# Stepper_Motor3.net
KiCad netlist of a schematic drawn in Altium Designer
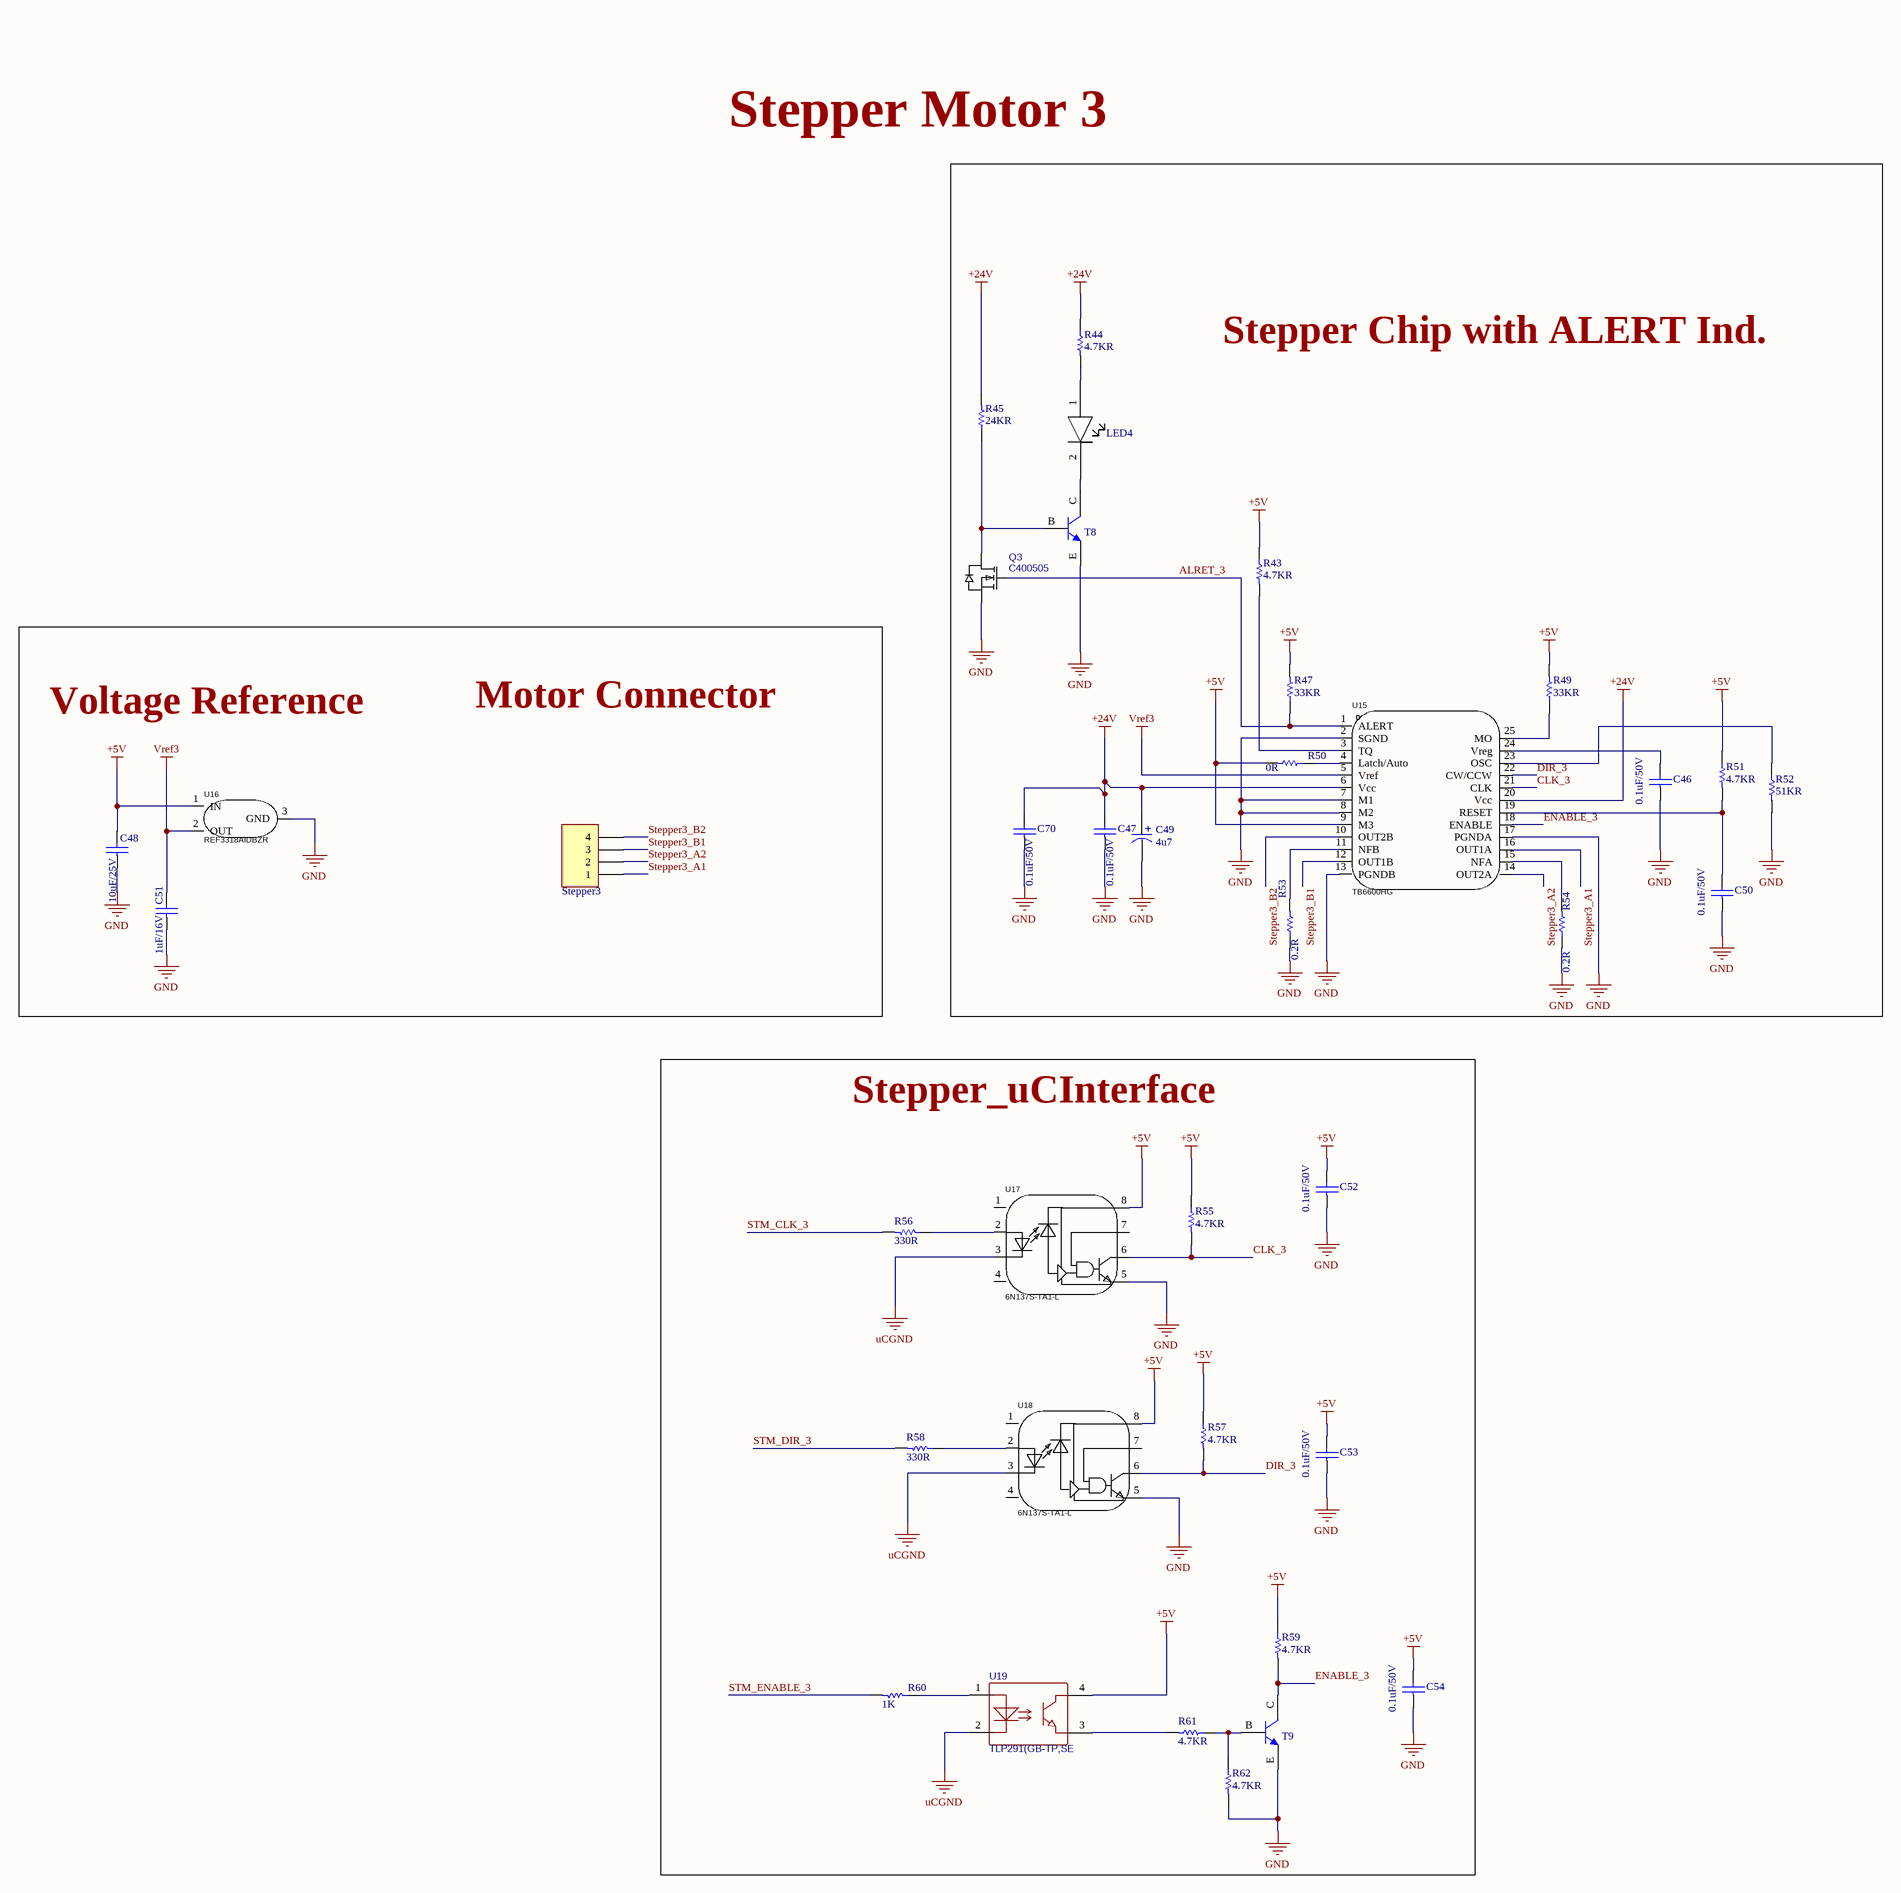
[diagram p0: Stepper Motor3.SchDoc]

(export (version "E")
  (design (tool "Eeschema 10.0.6"))
  (components
    (comp (ref "C46")
      (value "0.1uF/50V")
      (footprint "PCBComponent_1")
      (description "C1591")
      (fields (field (name "CREATED BY") "NourAldin"))
      (libsource (lib "0603 Capacitor") (part "0603 Capacitor"))
    )
    (comp (ref "C47")
      (value "0.1uF/50V")
      (footprint "PCBComponent_1")
      (description "C1591")
      (fields (field (name "CREATED BY") "NourAldin"))
      (libsource (lib "0603 Capacitor") (part "0603 Capacitor"))
    )
    (comp (ref "C48")
      (value "10uF/25V")
      (footprint "PCBComponent_1")
      (description "C96446")
      (fields (field (name "CREATED BY") "NourAldin"))
      (libsource (lib "0603 Capacitor") (part "0603 Capacitor"))
    )
    (comp (ref "C49")
      (value "4u7")
      (footprint "CAPLEAD_D6.3mm")
      (description "C2691843")
      (fields
        (field (name "MANUFACTURER") "KEMET")
        (field (name "MANUFACTURER PART NUMBER") "A759EQ475M2AAAE160")
      )
      (libsource (lib "GlobalLib") (part "A759EQ475M2AAAE160"))
    )
    (comp (ref "C50")
      (value "0.1uF/50V")
      (footprint "PCBComponent_1")
      (description "C1591")
      (fields (field (name "CREATED BY") "NourAldin"))
      (libsource (lib "0603 Capacitor") (part "0603 Capacitor"))
    )
    (comp (ref "C51")
      (value "1uF/16V")
      (footprint "PCBComponent_1")
      (description "C1592")
      (fields (field (name "CREATED BY") "NourAldin"))
      (libsource (lib "0603 Capacitor") (part "0603 Capacitor"))
    )
    (comp (ref "C52")
      (value "0.1uF/50V")
      (footprint "PCBComponent_1")
      (description "C1591")
      (fields (field (name "CREATED BY") "NourAldin"))
      (libsource (lib "0603 Capacitor") (part "0603 Capacitor"))
    )
    (comp (ref "C53")
      (value "0.1uF/50V")
      (footprint "PCBComponent_1")
      (description "C1591")
      (fields (field (name "CREATED BY") "NourAldin"))
      (libsource (lib "0603 Capacitor") (part "0603 Capacitor"))
    )
    (comp (ref "C54")
      (value "0.1uF/50V")
      (footprint "PCBComponent_1")
      (description "C1591")
      (fields (field (name "CREATED BY") "NourAldin"))
      (libsource (lib "0603 Capacitor") (part "0603 Capacitor"))
    )
    (comp (ref "C70")
      (value "0.1uF/50V")
      (footprint "PCBComponent_1")
      (description "C1591")
      (fields (field (name "CREATED BY") "NourAldin"))
      (libsource (lib "0603 Capacitor") (part "0603 Capacitor"))
    )
    (comp (ref "LED4")
      (value "1206 LED")
      (footprint "1206 LED")
      (description "C434438")
      (fields (field (name "CREATED BY") "NourAldin"))
      (libsource (lib "1206 LED") (part "1206 LED"))
    )
    (comp (ref "Q3")
      (value "C400505")
      (footprint "SOT-23-3_L2.9-W1.3-P1.90-LS2.4-BR")
      (fields
        (field (name "MANUFACTURER") "YANGJIE(扬杰)")
        (field (name "MANUFACTURER PART") "BSS138")
        (field (name "CONTRIBUTOR") "LCSC")
      )
      (libsource (lib "DIVERSE") (part "BSS138_MOSFET"))
    )
    (comp (ref "R43")
      (value "4.7KR")
      (footprint "R0402")
      (description "C105871")
      (libsource (lib "DIVERSE") (part "0402 Resistor"))
    )
    (comp (ref "R44")
      (value "4.7KR")
      (footprint "R0402")
      (description "C105871")
      (libsource (lib "DIVERSE") (part "0402 Resistor"))
    )
    (comp (ref "R45")
      (value "24KR")
      (footprint "RESC1608X06N")
      (description "C2930081")
      (fields (field (name "CREATED BY") "NourAldin"))
      (libsource (lib "0603 Resistor") (part "0603 Resistor"))
    )
    (comp (ref "R47")
      (value "33KR")
      (footprint "RESC1608X06N")
      (description "C126359")
      (fields (field (name "CREATED BY") "NourAldin"))
      (libsource (lib "0603 Resistor") (part "0603 Resistor"))
    )
    (comp (ref "R49")
      (value "33KR")
      (footprint "RESC1608X06N")
      (description "C126359")
      (fields (field (name "CREATED BY") "NourAldin"))
      (libsource (lib "0603 Resistor") (part "0603 Resistor"))
    )
    (comp (ref "R50")
      (value "0R")
      (footprint "RESC1608X06N")
      (description "C100044")
      (fields (field (name "CREATED BY") "NourAldin"))
      (libsource (lib "0603 Resistor") (part "0603 Resistor"))
    )
    (comp (ref "R51")
      (value "4.7KR")
      (footprint "R0402")
      (description "C105871")
      (libsource (lib "DIVERSE") (part "0402 Resistor"))
    )
    (comp (ref "R52")
      (value "51KR")
      (footprint "R0402")
      (description "C107230")
      (libsource (lib "DIVERSE") (part "0402 Resistor"))
    )
    (comp (ref "R53")
      (value "0.2R")
      (footprint "RESC6431X12N")
      (description "C2903473")
      (fields (field (name "CREATED BY") "NourAldin"))
      (libsource (lib "2512 Resistor") (part "2512 Resistor"))
    )
    (comp (ref "R54")
      (value "0.2R")
      (footprint "RESC6431X12N")
      (description "C2903473")
      (fields (field (name "CREATED BY") "NourAldin"))
      (libsource (lib "2512 Resistor") (part "2512 Resistor"))
    )
    (comp (ref "R55")
      (value "4.7KR")
      (footprint "R0402")
      (description "C105871")
      (libsource (lib "DIVERSE") (part "0402 Resistor"))
    )
    (comp (ref "R56")
      (value "330R")
      (footprint "R0402")
      (description "C105875")
      (libsource (lib "DIVERSE") (part "0402 Resistor"))
    )
    (comp (ref "R57")
      (value "4.7KR")
      (footprint "R0402")
      (description "C105871")
      (libsource (lib "DIVERSE") (part "0402 Resistor"))
    )
    (comp (ref "R58")
      (value "330R")
      (footprint "R0402")
      (description "C105875")
      (libsource (lib "DIVERSE") (part "0402 Resistor"))
    )
    (comp (ref "R59")
      (value "4.7KR")
      (footprint "R0402")
      (description "C105871")
      (libsource (lib "DIVERSE") (part "0402 Resistor"))
    )
    (comp (ref "R60")
      (value "1K")
      (footprint "R0402")
      (description "C106235")
      (libsource (lib "DIVERSE") (part "0402 Resistor"))
    )
    (comp (ref "R61")
      (value "4.7KR")
      (footprint "R0402")
      (description "C105871")
      (libsource (lib "DIVERSE") (part "0402 Resistor"))
    )
    (comp (ref "R62")
      (value "4.7KR")
      (footprint "R0402")
      (description "C105871")
      (libsource (lib "DIVERSE") (part "0402 Resistor"))
    )
    (comp (ref "Stepper3")
      (value "Header 4 Pin Polar")
      (footprint "PCBComponent_1")
      (description "C144395")
      (libsource (lib "Header 4 Pin Polar") (part "Header 4 Pin Polar"))
    )
    (comp (ref "T8")
      (value "MMBT3904 Transistor")
      (footprint "MMBT3904")
      (description "C108429")
      (fields (field (name "CREATED BY") "NourAldin"))
      (libsource (lib "MMBT3904 Transistor") (part "MMBT3904 Transistor"))
    )
    (comp (ref "T9")
      (value "MMBT3904 Transistor")
      (footprint "MMBT3904")
      (description "C108429")
      (fields (field (name "CREATED BY") "NourAldin"))
      (libsource (lib "MMBT3904 Transistor") (part "MMBT3904 Transistor"))
    )
    (comp (ref "U15")
      (value "TB6600HG")
      (footprint "HZIP25-P-1.0_TB6600HG - HEATSINK")
      (description "C66042")
      (fields (field (name "MANUFACTURER") "TOSHIBA(东芝)"))
      (libsource (lib "LIB") (part "TB6600HG"))
    )
    (comp (ref "U16")
      (value "REF3318AIDBZR")
      (footprint "SOT-23-3_L2.9-W1.3-P1.90-LS2.4-BR")
      (description "C115877")
      (fields (field (name "MANUFACTURER") "TI(德州仪器)") (field (name "TOLERANCE") "±0.15%"))
      (libsource (lib "LIB") (part "REF3318AIDBZR"))
    )
    (comp (ref "U17")
      (value "6N137S-TA1-L")
      (footprint "SOP-8_L9.8-W6.6-P2.54-LS10.3-BL")
      (description "C92651")
      (fields (field (name "MANUFACTURER") "LITEON(光宝)"))
      (libsource (lib "LIB") (part "6N137S-TA1-L"))
    )
    (comp (ref "U18")
      (value "6N137S-TA1-L")
      (footprint "SOP-8_L9.8-W6.6-P2.54-LS10.3-BL")
      (description "C92651")
      (fields (field (name "MANUFACTURER") "LITEON(光宝)"))
      (libsource (lib "LIB") (part "6N137S-TA1-L"))
    )
    (comp (ref "U19")
      (value "TLP291(GB-TP,SE")
      (footprint "SOP-4-1.27mm")
      (description "C55144")
      (libsource (lib "CO2_Lib") (part "TLP291(GB-TP,SE(T"))
    )
  )
  (nets
    (net (code "1") (name "+5V") (class "Default")
      (node (ref "C48") (pin "2") (pinfunction "2_2") (pintype "passive"))
      (node (ref "C52") (pin "2") (pinfunction "2_2") (pintype "passive"))
      (node (ref "C53") (pin "2") (pinfunction "2_2") (pintype "passive"))
      (node (ref "C54") (pin "2") (pinfunction "2_2") (pintype "passive"))
      (node (ref "R43") (pin "1") (pinfunction "1_1") (pintype "passive"))
      (node (ref "R47") (pin "2") (pinfunction "2_2") (pintype "passive"))
      (node (ref "R49") (pin "2") (pinfunction "2_2") (pintype "passive"))
      (node (ref "R50") (pin "2") (pinfunction "2_2") (pintype "passive"))
      (node (ref "R51") (pin "1") (pinfunction "1_1") (pintype "passive"))
      (node (ref "R55") (pin "1") (pinfunction "1_1") (pintype "passive"))
      (node (ref "R57") (pin "1") (pinfunction "1_1") (pintype "passive"))
      (node (ref "R59") (pin "1") (pinfunction "1_1") (pintype "passive"))
      (node (ref "U15") (pin "9") (pinfunction "M3_9") (pintype "passive"))
      (node (ref "U16") (pin "1") (pinfunction "IN_1") (pintype "passive"))
      (node (ref "U17") (pin "8") (pinfunction "8_8") (pintype "passive"))
      (node (ref "U18") (pin "8") (pinfunction "8_8") (pintype "passive"))
      (node (ref "U19") (pin "4") (pinfunction "4_4") (pintype "passive"))
    )
    (net (code "2") (name "+24V") (class "Default")
      (node (ref "C47") (pin "2") (pinfunction "2_2") (pintype "passive"))
      (node (ref "C49") (pin "1") (pinfunction "1_1") (pintype "passive"))
      (node (ref "C70") (pin "2") (pinfunction "2_2") (pintype "passive"))
      (node (ref "R44") (pin "1") (pinfunction "1_1") (pintype "passive"))
      (node (ref "R45") (pin "2") (pinfunction "2_2") (pintype "passive"))
      (node (ref "U15") (pin "20") (pinfunction "Vcc_20") (pintype "passive"))
      (node (ref "U15") (pin "6") (pinfunction "Vcc_6") (pintype "passive"))
    )
    (net (code "3") (name "/ALRET_3") (class "Default")
      (node (ref "Q3") (pin "1") (pinfunction "G_1") (pintype "passive"))
      (node (ref "R47") (pin "1") (pinfunction "1_1") (pintype "passive"))
      (node (ref "U15") (pin "1") (pinfunction "ALERT_1") (pintype "passive"))
    )
    (net (code "4") (name "/CLK_3") (class "Default")
      (node (ref "R55") (pin "2") (pinfunction "2_2") (pintype "passive"))
      (node (ref "U15") (pin "21") (pinfunction "CLK_21") (pintype "passive"))
      (node (ref "U17") (pin "6") (pinfunction "6_6") (pintype "passive"))
    )
    (net (code "5") (name "/DIR_3") (class "Default")
      (node (ref "R57") (pin "2") (pinfunction "2_2") (pintype "passive"))
      (node (ref "U15") (pin "22") (pinfunction "CW/CCW_22") (pintype "passive"))
      (node (ref "U18") (pin "6") (pinfunction "6_6") (pintype "passive"))
    )
    (net (code "6") (name "/ENABLE_3") (class "Default")
      (node (ref "R59") (pin "2") (pinfunction "2_2") (pintype "passive"))
      (node (ref "T9") (pin "C") (pinfunction "C_C") (pintype "passive"))
      (node (ref "U15") (pin "18") (pinfunction "ENABLE_18") (pintype "passive"))
    )
    (net (code "7") (name "/STM_CLK_3") (class "Default")
      (node (ref "R56") (pin "2") (pinfunction "2_2") (pintype "passive"))
    )
    (net (code "8") (name "/STM_DIR_3") (class "Default")
      (node (ref "R58") (pin "2") (pinfunction "2_2") (pintype "passive"))
    )
    (net (code "9") (name "/STM_ENABLE_3") (class "Default")
      (node (ref "R60") (pin "2") (pinfunction "2_2") (pintype "passive"))
    )
    (net (code "10") (name "/Stepper3_A1") (class "Default")
      (node (ref "Stepper3") (pin "1") (pinfunction "1_1") (pintype "passive"))
      (node (ref "U15") (pin "16") (pinfunction "OUT1A_16") (pintype "passive"))
    )
    (net (code "11") (name "/Stepper3_A2") (class "Default")
      (node (ref "Stepper3") (pin "2") (pinfunction "2_2") (pintype "passive"))
      (node (ref "U15") (pin "14") (pinfunction "OUT2A_14") (pintype "passive"))
    )
    (net (code "12") (name "/Stepper3_B1") (class "Default")
      (node (ref "Stepper3") (pin "3") (pinfunction "3_3") (pintype "passive"))
      (node (ref "U15") (pin "12") (pinfunction "OUT1B_12") (pintype "passive"))
    )
    (net (code "13") (name "/Stepper3_B2") (class "Default")
      (node (ref "Stepper3") (pin "4") (pinfunction "4_4") (pintype "passive"))
      (node (ref "U15") (pin "10") (pinfunction "OUT2B_10") (pintype "passive"))
    )
    (net (code "14") (name "GND") (class "Default")
      (node (ref "C46") (pin "1") (pinfunction "1_1") (pintype "passive"))
      (node (ref "C47") (pin "1") (pinfunction "1_1") (pintype "passive"))
      (node (ref "C48") (pin "1") (pinfunction "1_1") (pintype "passive"))
      (node (ref "C49") (pin "2") (pinfunction "2_2") (pintype "passive"))
      (node (ref "C50") (pin "1") (pinfunction "1_1") (pintype "passive"))
      (node (ref "C51") (pin "1") (pinfunction "1_1") (pintype "passive"))
      (node (ref "C52") (pin "1") (pinfunction "1_1") (pintype "passive"))
      (node (ref "C53") (pin "1") (pinfunction "1_1") (pintype "passive"))
      (node (ref "C54") (pin "1") (pinfunction "1_1") (pintype "passive"))
      (node (ref "C70") (pin "1") (pinfunction "1_1") (pintype "passive"))
      (node (ref "Q3") (pin "2") (pinfunction "S_2") (pintype "passive"))
      (node (ref "R52") (pin "2") (pinfunction "2_2") (pintype "passive"))
      (node (ref "R53") (pin "1") (pinfunction "1_1") (pintype "passive"))
      (node (ref "R54") (pin "1") (pinfunction "1_1") (pintype "passive"))
      (node (ref "R62") (pin "2") (pinfunction "2_2") (pintype "passive"))
      (node (ref "T8") (pin "E") (pinfunction "E_E") (pintype "passive"))
      (node (ref "T9") (pin "E") (pinfunction "E_E") (pintype "passive"))
      (node (ref "U15") (pin "13") (pinfunction "PGNDB_13") (pintype "passive"))
      (node (ref "U15") (pin "17") (pinfunction "PGNDA_17") (pintype "passive"))
      (node (ref "U15") (pin "2") (pinfunction "SGND_2") (pintype "passive"))
      (node (ref "U15") (pin "7") (pinfunction "M1_7") (pintype "passive"))
      (node (ref "U15") (pin "8") (pinfunction "M2_8") (pintype "passive"))
      (node (ref "U16") (pin "3") (pinfunction "GND_3") (pintype "passive"))
      (node (ref "U17") (pin "5") (pinfunction "5_5") (pintype "passive"))
      (node (ref "U18") (pin "5") (pinfunction "5_5") (pintype "passive"))
    )
    (net (code "15") (name "Net-(LED4-Pad1)") (class "Default")
      (node (ref "LED4") (pin "1") (pinfunction "1_1") (pintype "passive"))
      (node (ref "R44") (pin "2") (pinfunction "2_2") (pintype "passive"))
    )
    (net (code "16") (name "Net-(LED4-Pad2)") (class "Default")
      (node (ref "LED4") (pin "2") (pinfunction "2_2") (pintype "passive"))
      (node (ref "T8") (pin "C") (pinfunction "C_C") (pintype "passive"))
    )
    (net (code "17") (name "Net-(Q3-D)") (class "Default")
      (node (ref "Q3") (pin "3") (pinfunction "D_3") (pintype "passive"))
      (node (ref "R45") (pin "1") (pinfunction "1_1") (pintype "passive"))
      (node (ref "T8") (pin "B") (pinfunction "B_B") (pintype "passive"))
    )
    (net (code "18") (name "Net-(R56-Pad1)") (class "Default")
      (node (ref "R56") (pin "1") (pinfunction "1_1") (pintype "passive"))
      (node (ref "U17") (pin "2") (pinfunction "2_2") (pintype "passive"))
    )
    (net (code "19") (name "Net-(R58-Pad1)") (class "Default")
      (node (ref "R58") (pin "1") (pinfunction "1_1") (pintype "passive"))
      (node (ref "U18") (pin "2") (pinfunction "2_2") (pintype "passive"))
    )
    (net (code "20") (name "Net-(R60-Pad1)") (class "Default")
      (node (ref "R60") (pin "1") (pinfunction "1_1") (pintype "passive"))
      (node (ref "U19") (pin "1") (pinfunction "1_1") (pintype "passive"))
    )
    (net (code "21") (name "Net-(R61-Pad1)") (class "Default")
      (node (ref "R61") (pin "1") (pinfunction "1_1") (pintype "passive"))
      (node (ref "R62") (pin "1") (pinfunction "1_1") (pintype "passive"))
      (node (ref "T9") (pin "B") (pinfunction "B_B") (pintype "passive"))
    )
    (net (code "22") (name "Net-(R61-Pad2)") (class "Default")
      (node (ref "R61") (pin "2") (pinfunction "2_2") (pintype "passive"))
      (node (ref "U19") (pin "3") (pinfunction "3_3") (pintype "passive"))
    )
    (net (code "23") (name "Net-(U15-Latch{slash}Auto)") (class "Default")
      (node (ref "R50") (pin "1") (pinfunction "1_1") (pintype "passive"))
      (node (ref "U15") (pin "4") (pinfunction "Latch/Auto_4") (pintype "passive"))
    )
    (net (code "24") (name "Net-(U15-MO)") (class "Default")
      (node (ref "R49") (pin "1") (pinfunction "1_1") (pintype "passive"))
      (node (ref "U15") (pin "25") (pinfunction "MO_25") (pintype "passive"))
    )
    (net (code "25") (name "Net-(U15-NFA)") (class "Default")
      (node (ref "R54") (pin "2") (pinfunction "2_2") (pintype "passive"))
      (node (ref "U15") (pin "15") (pinfunction "NFA_15") (pintype "passive"))
    )
    (net (code "26") (name "Net-(U15-NFB)") (class "Default")
      (node (ref "R53") (pin "2") (pinfunction "2_2") (pintype "passive"))
      (node (ref "U15") (pin "11") (pinfunction "NFB_11") (pintype "passive"))
    )
    (net (code "27") (name "Net-(U15-OSC)") (class "Default")
      (node (ref "R52") (pin "1") (pinfunction "1_1") (pintype "passive"))
      (node (ref "U15") (pin "23") (pinfunction "OSC_23") (pintype "passive"))
    )
    (net (code "28") (name "Net-(U15-RESET)") (class "Default")
      (node (ref "C50") (pin "2") (pinfunction "2_2") (pintype "passive"))
      (node (ref "R51") (pin "2") (pinfunction "2_2") (pintype "passive"))
      (node (ref "U15") (pin "19") (pinfunction "RESET_19") (pintype "passive"))
    )
    (net (code "29") (name "Net-(U15-TQ)") (class "Default")
      (node (ref "R43") (pin "2") (pinfunction "2_2") (pintype "passive"))
      (node (ref "U15") (pin "3") (pinfunction "TQ_3") (pintype "passive"))
    )
    (net (code "30") (name "Net-(U15-Vreg)") (class "Default")
      (node (ref "C46") (pin "2") (pinfunction "2_2") (pintype "passive"))
      (node (ref "U15") (pin "24") (pinfunction "Vreg_24") (pintype "passive"))
    )
    (net (code "31") (name "Vref3") (class "Default")
      (node (ref "C51") (pin "2") (pinfunction "2_2") (pintype "passive"))
      (node (ref "U15") (pin "5") (pinfunction "Vref_5") (pintype "passive"))
      (node (ref "U16") (pin "2") (pinfunction "OUT_2") (pintype "passive"))
    )
    (net (code "32") (name "uCGND") (class "Default")
      (node (ref "U17") (pin "3") (pinfunction "3_3") (pintype "passive"))
      (node (ref "U18") (pin "3") (pinfunction "3_3") (pintype "passive"))
      (node (ref "U19") (pin "2") (pinfunction "2_2") (pintype "passive"))
    )
    (net (code "33") (name "unconnected-(U17-NC-Pad1)") (class "Default")
      (node (ref "U17") (pin "1") (pinfunction "NC_1") (pintype "passive"))
    )
    (net (code "34") (name "unconnected-(U17-NC-Pad4)") (class "Default")
      (node (ref "U17") (pin "4") (pinfunction "NC_4") (pintype "passive"))
    )
    (net (code "35") (name "unconnected-(U17-Pad7)") (class "Default")
      (node (ref "U17") (pin "7") (pinfunction "7_7") (pintype "passive"))
    )
    (net (code "36") (name "unconnected-(U18-NC-Pad1)") (class "Default")
      (node (ref "U18") (pin "1") (pinfunction "NC_1") (pintype "passive"))
    )
    (net (code "37") (name "unconnected-(U18-NC-Pad4)") (class "Default")
      (node (ref "U18") (pin "4") (pinfunction "NC_4") (pintype "passive"))
    )
    (net (code "38") (name "unconnected-(U18-Pad7)") (class "Default")
      (node (ref "U18") (pin "7") (pinfunction "7_7") (pintype "passive"))
    )
  )
)
